# main_board.net
KiCad netlist of a schematic drawn in EAGLE
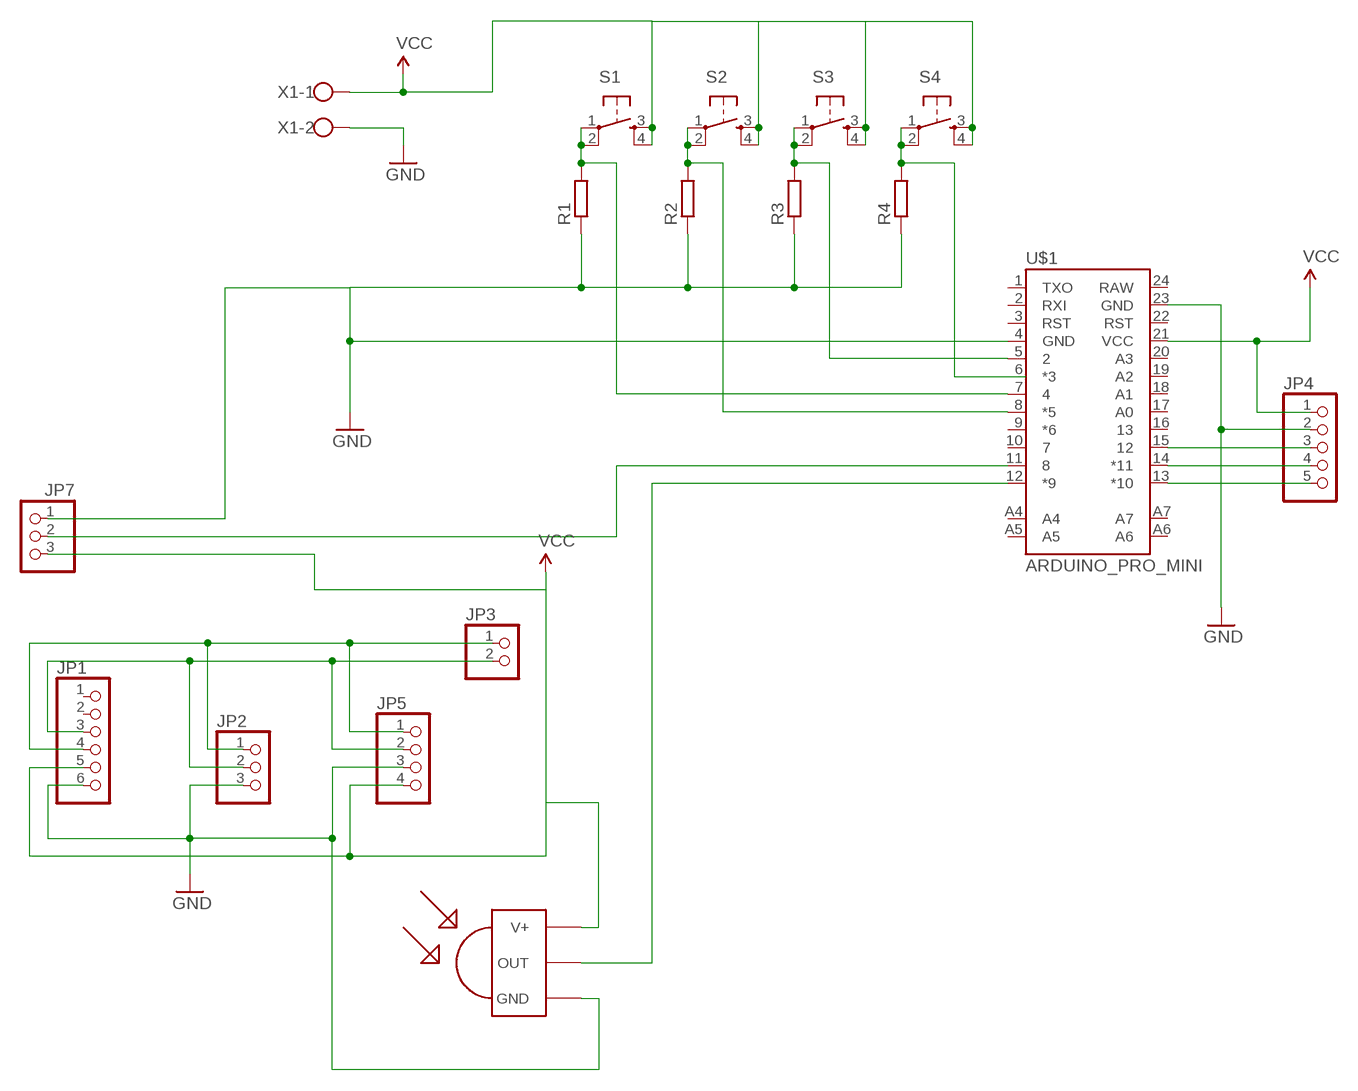
[diagram p0: schematic, sheet 1]

(export (version "E")
  (design (tool "Eeschema 10.0.6"))
  (components
    (comp (ref "JP1")
      (value "PINHD-1X6")
      (footprint "eagle-import:1X06")
      (libsource (lib "eagle-import") (part "PINHD-1X6"))
    )
    (comp (ref "JP2")
      (value "PINHD-1X3")
      (footprint "eagle-import:1X03")
      (libsource (lib "eagle-import") (part "PINHD-1X3"))
    )
    (comp (ref "JP3")
      (value "PINHD-1X2")
      (footprint "eagle-import:1X02")
      (libsource (lib "eagle-import") (part "PINHD-1X2"))
    )
    (comp (ref "JP4")
      (value "PINHD-1X5")
      (footprint "eagle-import:1X05")
      (libsource (lib "eagle-import") (part "PINHD-1X5"))
    )
    (comp (ref "JP5")
      (value "PINHD-1X4")
      (footprint "eagle-import:1X04")
      (libsource (lib "eagle-import") (part "PINHD-1X4"))
    )
    (comp (ref "JP7")
      (value "PINHD-1X3")
      (footprint "eagle-import:1X03")
      (libsource (lib "eagle-import") (part "PINHD-1X3"))
    )
    (comp (ref "R1")
      (value "R0207/10")
      (footprint "eagle-import:0207_10")
      (libsource (lib "eagle-import") (part "R0207/10"))
    )
    (comp (ref "R2")
      (value "R0207/10")
      (footprint "eagle-import:0207_10")
      (libsource (lib "eagle-import") (part "R0207/10"))
    )
    (comp (ref "R3")
      (value "R0207/10")
      (footprint "eagle-import:0207_10")
      (libsource (lib "eagle-import") (part "R0207/10"))
    )
    (comp (ref "R4")
      (value "R0207/10")
      (footprint "eagle-import:0207_10")
      (libsource (lib "eagle-import") (part "R0207/10"))
    )
    (comp (ref "S1")
      (value "TAC_SWITCHPTH")
      (footprint "eagle-import:TACTILE-PTH")
      (libsource (lib "eagle-import") (part "TAC_SWITCHPTH"))
    )
    (comp (ref "S2")
      (value "TAC_SWITCHPTH")
      (footprint "eagle-import:TACTILE-PTH")
      (libsource (lib "eagle-import") (part "TAC_SWITCHPTH"))
    )
    (comp (ref "S3")
      (value "TAC_SWITCHPTH")
      (footprint "eagle-import:TACTILE-PTH")
      (libsource (lib "eagle-import") (part "TAC_SWITCHPTH"))
    )
    (comp (ref "S4")
      (value "TAC_SWITCHPTH")
      (footprint "eagle-import:TACTILE-PTH")
      (libsource (lib "eagle-import") (part "TAC_SWITCHPTH"))
    )
    (comp (ref "U$1")
      (value "ARDUINO_PRO_MINI")
      (footprint "eagle-import:ARDUINO_PRO_MINI")
      (libsource (lib "eagle-import") (part "ARDUINO_PRO_MINI"))
    )
    (comp (ref "U$2")
      (value "TSOP1736")
      (footprint "eagle-import:TSOP17XX")
      (libsource (lib "eagle-import") (part "TSOP1736"))
    )
    (comp (ref "X1")
      (value "W237-102")
      (footprint "eagle-import:W237-102")
      (fields (field (name "MPN") "237-102"))
      (libsource (lib "eagle-import") (part "W237-102"))
    )
  )
  (nets
    (net (code "1") (name "GND") (class "Default")
      (node (ref "JP1") (pin "6") (pinfunction "6_6") (pintype "passive"))
      (node (ref "JP2") (pin "3") (pinfunction "3_3") (pintype "passive"))
      (node (ref "JP4") (pin "2") (pinfunction "2_2") (pintype "passive"))
      (node (ref "JP5") (pin "3") (pinfunction "3_3") (pintype "passive"))
      (node (ref "JP7") (pin "1") (pinfunction "1_1") (pintype "passive"))
      (node (ref "R1") (pin "1") (pinfunction "1_1") (pintype "passive"))
      (node (ref "R2") (pin "1") (pinfunction "1_1") (pintype "passive"))
      (node (ref "R3") (pin "1") (pinfunction "1_1") (pintype "passive"))
      (node (ref "R4") (pin "1") (pinfunction "1_1") (pintype "passive"))
      (node (ref "U$1") (pin "23") (pinfunction "GND_23") (pintype "bidirectional"))
      (node (ref "U$1") (pin "4") (pinfunction "GND_4") (pintype "bidirectional"))
      (node (ref "U$2") (pin "GND") (pinfunction "GND_GND") (pintype "bidirectional"))
      (node (ref "X1") (pin "2") (pinfunction "KL_2") (pintype "passive"))
    )
    (net (code "2") (name "Net-(JP1-Pad3)") (class "Default")
      (node (ref "JP1") (pin "3") (pinfunction "3_3") (pintype "passive"))
      (node (ref "JP2") (pin "2") (pinfunction "2_2") (pintype "passive"))
      (node (ref "JP3") (pin "2") (pinfunction "2_2") (pintype "passive"))
      (node (ref "JP5") (pin "2") (pinfunction "2_2") (pintype "passive"))
    )
    (net (code "3") (name "Net-(JP1-Pad4)") (class "Default")
      (node (ref "JP1") (pin "4") (pinfunction "4_4") (pintype "passive"))
      (node (ref "JP2") (pin "1") (pinfunction "1_1") (pintype "passive"))
      (node (ref "JP3") (pin "1") (pinfunction "1_1") (pintype "passive"))
      (node (ref "JP5") (pin "1") (pinfunction "1_1") (pintype "passive"))
    )
    (net (code "4") (name "Net-(R4-Pad2)") (class "Default")
      (node (ref "R4") (pin "2") (pinfunction "2_2") (pintype "passive"))
      (node (ref "S4") (pin "1") (pinfunction "1_1") (pintype "passive"))
      (node (ref "S4") (pin "2") (pinfunction "2_2") (pintype "passive"))
    )
    (net (code "5") (name "Net-(U$1-*5)") (class "Default")
      (node (ref "R2") (pin "2") (pinfunction "2_2") (pintype "passive"))
      (node (ref "S2") (pin "1") (pinfunction "1_1") (pintype "passive"))
      (node (ref "S2") (pin "2") (pinfunction "2_2") (pintype "passive"))
      (node (ref "U$1") (pin "8") (pinfunction "*5_8") (pintype "bidirectional"))
    )
    (net (code "6") (name "Net-(U$1-*9)") (class "Default")
      (node (ref "U$1") (pin "12") (pinfunction "*9_12") (pintype "bidirectional"))
      (node (ref "U$2") (pin "OUT") (pinfunction "OUT_OUT") (pintype "bidirectional"))
    )
    (net (code "7") (name "Net-(U$1-*10)") (class "Default")
      (node (ref "JP4") (pin "5") (pinfunction "5_5") (pintype "passive"))
      (node (ref "U$1") (pin "13") (pinfunction "*10_13") (pintype "bidirectional"))
    )
    (net (code "8") (name "Net-(U$1-*11)") (class "Default")
      (node (ref "JP4") (pin "4") (pinfunction "4_4") (pintype "passive"))
      (node (ref "U$1") (pin "14") (pinfunction "*11_14") (pintype "bidirectional"))
    )
    (net (code "9") (name "Net-(U$1-2)") (class "Default")
      (node (ref "R3") (pin "2") (pinfunction "2_2") (pintype "passive"))
      (node (ref "S3") (pin "1") (pinfunction "1_1") (pintype "passive"))
      (node (ref "S3") (pin "2") (pinfunction "2_2") (pintype "passive"))
      (node (ref "U$1") (pin "5") (pinfunction "2_5") (pintype "bidirectional"))
    )
    (net (code "10") (name "Net-(U$1-4)") (class "Default")
      (node (ref "R1") (pin "2") (pinfunction "2_2") (pintype "passive"))
      (node (ref "S1") (pin "1") (pinfunction "1_1") (pintype "passive"))
      (node (ref "S1") (pin "2") (pinfunction "2_2") (pintype "passive"))
      (node (ref "U$1") (pin "7") (pinfunction "4_7") (pintype "bidirectional"))
    )
    (net (code "11") (name "Net-(U$1-8)") (class "Default")
      (node (ref "JP7") (pin "2") (pinfunction "2_2") (pintype "passive"))
      (node (ref "U$1") (pin "11") (pinfunction "8_11") (pintype "bidirectional"))
    )
    (net (code "12") (name "Net-(U$1-12)") (class "Default")
      (node (ref "JP4") (pin "3") (pinfunction "3_3") (pintype "passive"))
      (node (ref "U$1") (pin "15") (pinfunction "12_15") (pintype "bidirectional"))
    )
    (net (code "13") (name "VCC") (class "Default")
      (node (ref "JP1") (pin "5") (pinfunction "5_5") (pintype "passive"))
      (node (ref "JP4") (pin "1") (pinfunction "1_1") (pintype "passive"))
      (node (ref "JP5") (pin "4") (pinfunction "4_4") (pintype "passive"))
      (node (ref "JP7") (pin "3") (pinfunction "3_3") (pintype "passive"))
      (node (ref "S1") (pin "3") (pinfunction "3_3") (pintype "passive"))
      (node (ref "S1") (pin "4") (pinfunction "4_4") (pintype "passive"))
      (node (ref "S2") (pin "3") (pinfunction "3_3") (pintype "passive"))
      (node (ref "S2") (pin "4") (pinfunction "4_4") (pintype "passive"))
      (node (ref "S3") (pin "3") (pinfunction "3_3") (pintype "passive"))
      (node (ref "S3") (pin "4") (pinfunction "4_4") (pintype "passive"))
      (node (ref "S4") (pin "3") (pinfunction "3_3") (pintype "passive"))
      (node (ref "S4") (pin "4") (pinfunction "4_4") (pintype "passive"))
      (node (ref "U$1") (pin "21") (pinfunction "VCC_21") (pintype "bidirectional"))
      (node (ref "U$2") (pin "V+") (pinfunction "V+_V+") (pintype "bidirectional"))
      (node (ref "X1") (pin "1") (pinfunction "KL_1") (pintype "passive"))
    )
    (net (code "14") (name "unconnected-(JP1-Pad1)") (class "Default")
      (node (ref "JP1") (pin "1") (pinfunction "1_1") (pintype "passive"))
    )
    (net (code "15") (name "unconnected-(JP1-Pad2)") (class "Default")
      (node (ref "JP1") (pin "2") (pinfunction "2_2") (pintype "passive"))
    )
    (net (code "16") (name "unconnected-(U$1-*3-Pad6)") (class "Default")
      (node (ref "U$1") (pin "6") (pinfunction "*3_6") (pintype "bidirectional"))
    )
    (net (code "17") (name "unconnected-(U$1-*6-Pad9)") (class "Default")
      (node (ref "U$1") (pin "9") (pinfunction "*6_9") (pintype "bidirectional"))
    )
    (net (code "18") (name "unconnected-(U$1-7-Pad10)") (class "Default")
      (node (ref "U$1") (pin "10") (pinfunction "7_10") (pintype "bidirectional"))
    )
    (net (code "19") (name "unconnected-(U$1-13-Pad16)") (class "Default")
      (node (ref "U$1") (pin "16") (pinfunction "13_16") (pintype "bidirectional"))
    )
    (net (code "20") (name "unconnected-(U$1-A0-Pad17)") (class "Default")
      (node (ref "U$1") (pin "17") (pinfunction "A0_17") (pintype "bidirectional"))
    )
    (net (code "21") (name "unconnected-(U$1-A1-Pad18)") (class "Default")
      (node (ref "U$1") (pin "18") (pinfunction "A1_18") (pintype "bidirectional"))
    )
    (net (code "22") (name "unconnected-(U$1-A2-Pad19)") (class "Default")
      (node (ref "U$1") (pin "19") (pinfunction "A2_19") (pintype "bidirectional"))
    )
    (net (code "23") (name "unconnected-(U$1-A3-Pad20)") (class "Default")
      (node (ref "U$1") (pin "20") (pinfunction "A3_20") (pintype "bidirectional"))
    )
    (net (code "24") (name "unconnected-(U$1-PadA4)") (class "Default")
      (node (ref "U$1") (pin "A4") (pinfunction "A4_A4") (pintype "bidirectional"))
    )
    (net (code "25") (name "unconnected-(U$1-PadA5)") (class "Default")
      (node (ref "U$1") (pin "A5") (pinfunction "A5_A5") (pintype "bidirectional"))
    )
    (net (code "26") (name "unconnected-(U$1-PadA6)") (class "Default")
      (node (ref "U$1") (pin "A6") (pinfunction "A6_A6") (pintype "bidirectional"))
    )
    (net (code "27") (name "unconnected-(U$1-PadA7)") (class "Default")
      (node (ref "U$1") (pin "A7") (pinfunction "A7_A7") (pintype "bidirectional"))
    )
    (net (code "28") (name "unconnected-(U$1-RAW-Pad24)") (class "Default")
      (node (ref "U$1") (pin "24") (pinfunction "RAW_24") (pintype "bidirectional"))
    )
    (net (code "29") (name "unconnected-(U$1-RST-Pad3)") (class "Default")
      (node (ref "U$1") (pin "3") (pinfunction "RST_3") (pintype "bidirectional"))
    )
    (net (code "30") (name "unconnected-(U$1-RST-Pad22)") (class "Default")
      (node (ref "U$1") (pin "22") (pinfunction "RST_22") (pintype "bidirectional"))
    )
    (net (code "31") (name "unconnected-(U$1-RXI-Pad2)") (class "Default")
      (node (ref "U$1") (pin "2") (pinfunction "RXI_2") (pintype "bidirectional"))
    )
    (net (code "32") (name "unconnected-(U$1-TXO-Pad1)") (class "Default")
      (node (ref "U$1") (pin "1") (pinfunction "TXO_1") (pintype "bidirectional"))
    )
  )
)
